# Power.net
KiCad netlist of a schematic drawn in Altium Designer
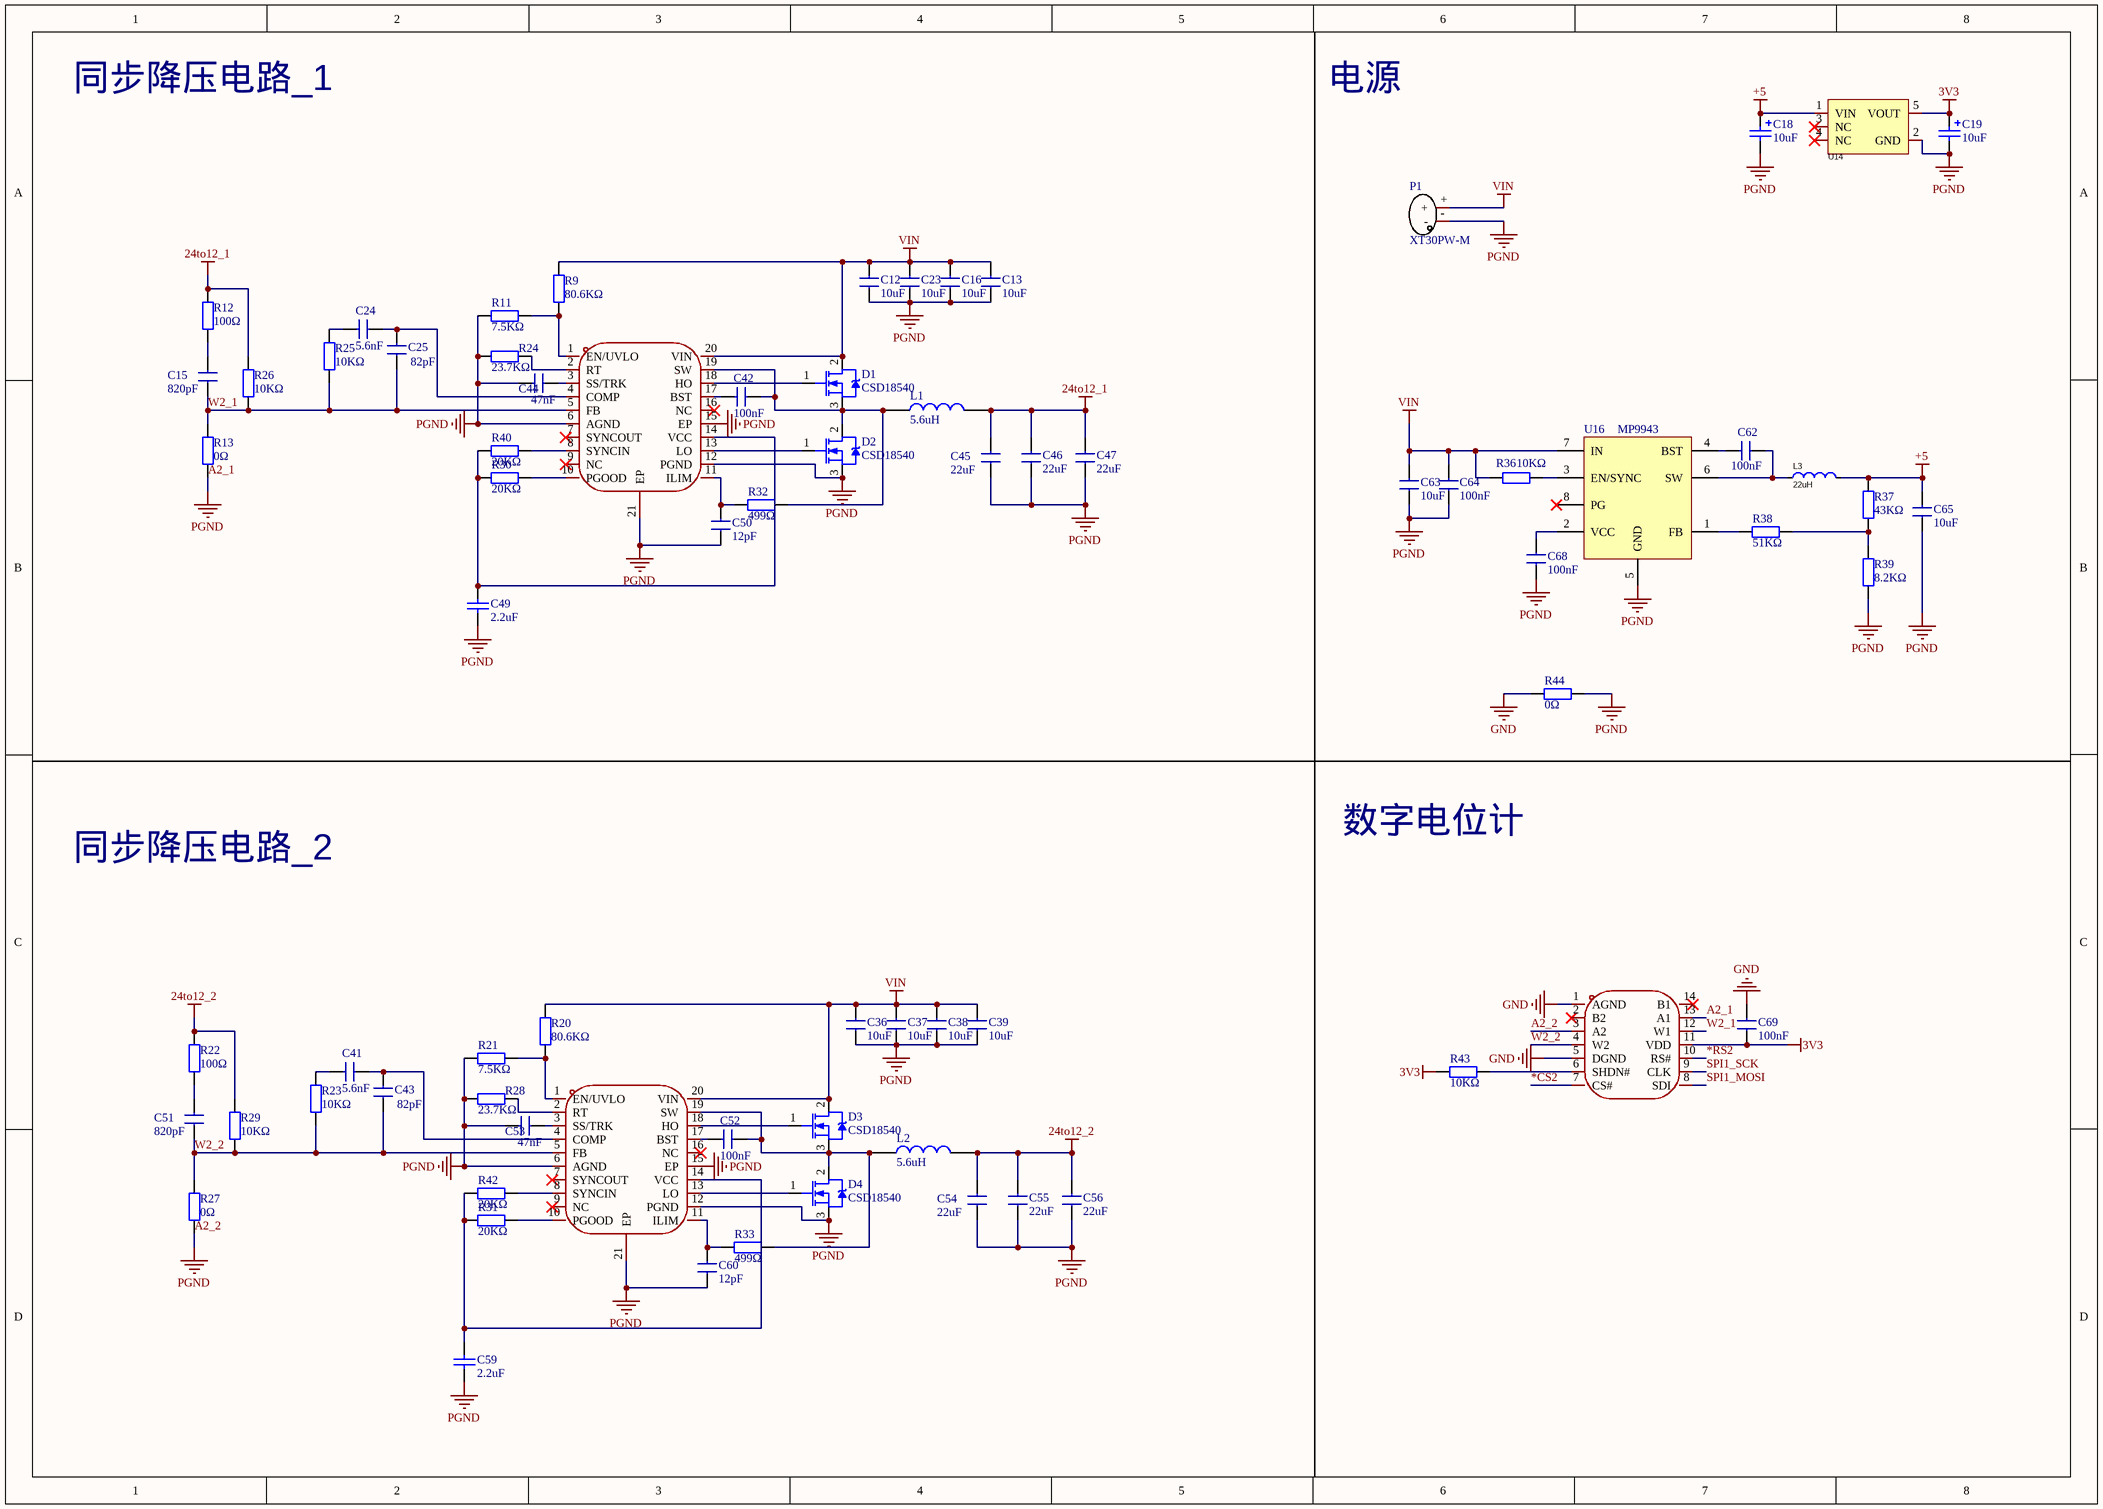
[diagram p0: Power.SchDoc]

(export (version "E")
  (design (tool "Eeschema 10.0.6"))
  (components
    (comp (ref "C12")
      (value "10uF")
      (footprint "1210")
      (description "1210贴片电容")
      (libsource (lib "Integrated_Library1") (part "1210贴片电容"))
    )
    (comp (ref "C13")
      (value "10uF")
      (footprint "1210")
      (description "1210贴片电容")
      (libsource (lib "En") (part "1210贴片电容"))
    )
    (comp (ref "C15")
      (value "820pF")
      (footprint "c0402")
      (description "贴片电容0402")
      (libsource (lib "Integrated_Library1") (part "0402贴片电容"))
    )
    (comp (ref "C16")
      (value "10uF")
      (footprint "1210")
      (description "1210贴片电容")
      (libsource (lib "En") (part "1210贴片电容"))
    )
    (comp (ref "C18")
      (value "10uF")
      (footprint "3216")
      (description "3216钽电容")
      (libsource (lib "Integrated_Library1") (part "3216钽电容"))
    )
    (comp (ref "C19")
      (value "10uF")
      (footprint "3216")
      (description "3216钽电容")
      (libsource (lib "Integrated_Library1") (part "3216钽电容"))
    )
    (comp (ref "C23")
      (value "10uF")
      (footprint "1210")
      (description "1210贴片电容")
      (libsource (lib "En") (part "1210贴片电容"))
    )
    (comp (ref "C24")
      (value "5.6nF")
      (footprint "c0402")
      (description "贴片电容0402")
      (libsource (lib "Integrated_Library1") (part "0402贴片电容"))
    )
    (comp (ref "C25")
      (value "82pF")
      (footprint "c0402")
      (description "贴片电容0402")
      (libsource (lib "Integrated_Library1") (part "0402贴片电容"))
    )
    (comp (ref "C36")
      (value "10uF")
      (footprint "1210")
      (description "1210贴片电容")
      (libsource (lib "Integrated_Library1") (part "1210贴片电容"))
    )
    (comp (ref "C37")
      (value "10uF")
      (footprint "1210")
      (description "1210贴片电容")
      (libsource (lib "En") (part "1210贴片电容"))
    )
    (comp (ref "C38")
      (value "10uF")
      (footprint "1210")
      (description "1210贴片电容")
      (libsource (lib "En") (part "1210贴片电容"))
    )
    (comp (ref "C39")
      (value "10uF")
      (footprint "1210")
      (description "1210贴片电容")
      (libsource (lib "En") (part "1210贴片电容"))
    )
    (comp (ref "C41")
      (value "5.6nF")
      (footprint "c0402")
      (description "贴片电容0402")
      (libsource (lib "Integrated_Library1") (part "0402贴片电容"))
    )
    (comp (ref "C42")
      (value "100nF")
      (footprint "C 0603_M")
      (description "贴片电容0402")
      (libsource (lib "Integrated_Library1") (part "0402贴片电容"))
    )
    (comp (ref "C43")
      (value "82pF")
      (footprint "c0402")
      (description "贴片电容0402")
      (libsource (lib "Integrated_Library1") (part "0402贴片电容"))
    )
    (comp (ref "C44")
      (value "47nF")
      (footprint "c0402")
      (description "贴片电容0402")
      (libsource (lib "Integrated_Library1") (part "0402贴片电容"))
    )
    (comp (ref "C45")
      (value "22uF")
      (footprint "1210")
      (description "1210贴片电容")
      (libsource (lib "En") (part "1210贴片电容"))
    )
    (comp (ref "C46")
      (value "22uF")
      (footprint "1210")
      (description "1210贴片电容")
      (libsource (lib "En") (part "1210贴片电容"))
    )
    (comp (ref "C47")
      (value "22uF")
      (footprint "1210")
      (description "1210贴片电容")
      (libsource (lib "En") (part "1210贴片电容"))
    )
    (comp (ref "C49")
      (value "2.2uF")
      (footprint "C 0603_M")
      (description "0603贴片电容")
      (libsource (lib "En") (part "0603贴片电容"))
    )
    (comp (ref "C50")
      (value "12pF")
      (footprint "c0402")
      (description "贴片电容0402")
      (libsource (lib "Integrated_Library1") (part "0402贴片电容"))
    )
    (comp (ref "C51")
      (value "820pF")
      (footprint "c0402")
      (description "贴片电容0402")
      (libsource (lib "Integrated_Library1") (part "0402贴片电容"))
    )
    (comp (ref "C52")
      (value "100nF")
      (footprint "C 0603_M")
      (description "贴片电容0402")
      (libsource (lib "Integrated_Library1") (part "0402贴片电容"))
    )
    (comp (ref "C53")
      (value "47nF")
      (footprint "c0402")
      (description "贴片电容0402")
      (libsource (lib "Integrated_Library1") (part "0402贴片电容"))
    )
    (comp (ref "C54")
      (value "22uF")
      (footprint "1210")
      (description "1210贴片电容")
      (libsource (lib "En") (part "1210贴片电容"))
    )
    (comp (ref "C55")
      (value "22uF")
      (footprint "1210")
      (description "1210贴片电容")
      (libsource (lib "En") (part "1210贴片电容"))
    )
    (comp (ref "C56")
      (value "22uF")
      (footprint "1210")
      (description "1210贴片电容")
      (libsource (lib "En") (part "1210贴片电容"))
    )
    (comp (ref "C59")
      (value "2.2uF")
      (footprint "C 0603_M")
      (description "0603贴片电容")
      (libsource (lib "En") (part "0603贴片电容"))
    )
    (comp (ref "C60")
      (value "12pF")
      (footprint "c0402")
      (description "贴片电容0402")
      (libsource (lib "Integrated_Library1") (part "0402贴片电容"))
    )
    (comp (ref "C62")
      (value "100nF")
      (footprint "c0402")
      (description "贴片电容0402")
      (libsource (lib "Integrated_Library1") (part "0402贴片电容"))
    )
    (comp (ref "C63")
      (value "10uF")
      (footprint "1210")
      (description "1210贴片电容")
      (libsource (lib "Integrated_Library1") (part "1210贴片电容"))
    )
    (comp (ref "C64")
      (value "100nF")
      (footprint "c0402")
      (description "贴片电容0402")
      (libsource (lib "Integrated_Library1") (part "0402贴片电容"))
    )
    (comp (ref "C65")
      (value "10uF")
      (footprint "1210")
      (description "1210贴片电容")
      (libsource (lib "Integrated_Library1") (part "1210贴片电容"))
    )
    (comp (ref "C68")
      (value "100nF")
      (footprint "c0402")
      (description "贴片电容0402")
      (libsource (lib "Integrated_Library1") (part "0402贴片电容"))
    )
    (comp (ref "C69")
      (value "100nF")
      (footprint "c0402")
      (description "贴片电容0402")
      (libsource (lib "Integrated_Library1") (part "0402贴片电容"))
    )
    (comp (ref "D1")
      (value "CSD18540")
      (footprint "pg-tdson-8")
      (description "N沟道MOS管")
      (fields (field (name "PUBLISHER") "Altium Limited"))
      (libsource (lib "En") (part "CSD18540"))
    )
    (comp (ref "D2")
      (value "CSD18540")
      (footprint "pg-tdson-8")
      (description "N沟道MOS管")
      (fields (field (name "PUBLISHER") "Altium Limited"))
      (libsource (lib "En") (part "CSD18540"))
    )
    (comp (ref "D3")
      (value "CSD18540")
      (footprint "pg-tdson-8")
      (description "N沟道MOS管")
      (fields (field (name "PUBLISHER") "Altium Limited"))
      (libsource (lib "En") (part "CSD18540"))
    )
    (comp (ref "D4")
      (value "CSD18540")
      (footprint "pg-tdson-8")
      (description "N沟道MOS管")
      (fields (field (name "PUBLISHER") "Altium Limited"))
      (libsource (lib "En") (part "CSD18540"))
    )
    (comp (ref "L1")
      (value "5.6uH")
      (footprint "L-SMD-0630")
      (description "一体成型屏蔽电感")
      (libsource (lib "En") (part "0630功率电感"))
    )
    (comp (ref "L2")
      (value "5.6uH")
      (footprint "L-SMD-0630")
      (description "一体成型屏蔽电感")
      (libsource (lib "En") (part "0630功率电感"))
    )
    (comp (ref "L3")
      (value "22uH")
      (footprint "IND-SMD_L5.4-W5.2")
      (description "一体成型屏蔽电感，0530封装，额定电流3A")
      (fields (field (name "MANUFACTURER") "XR(祥如)") (field (name "MANUFACTURER PART") "XR0530-100M"))
      (libsource (lib "En") (part "0530屏蔽电感"))
    )
    (comp (ref "P1")
      (value "XT30PW-M")
      (footprint "XT30PW-M")
      (description "卧式XT30母头")
      (fields (field (name "PUBLISHER") "Altium Limited"))
      (libsource (lib "Integrated_Library1") (part "卧式XT30母头"))
    )
    (comp (ref "R9")
      (value "80.6KΩ")
      (footprint "R0402")
      (description "0402贴片电阻")
      (libsource (lib "") (part "0402贴片电阻_3"))
    )
    (comp (ref "R11")
      (value "7.5KΩ")
      (footprint "R0402")
      (description "0402贴片电阻")
      (libsource (lib "") (part "0402贴片电阻_2"))
    )
    (comp (ref "R12")
      (value "100Ω")
      (footprint "R0402")
      (description "0402贴片电阻")
      (libsource (lib "Integrated_Library1") (part "0402贴片电阻"))
    )
    (comp (ref "R13")
      (value "0Ω")
      (footprint "R0402")
      (description "0402贴片电阻")
      (libsource (lib "") (part "0402贴片电阻_3"))
    )
    (comp (ref "R20")
      (value "80.6KΩ")
      (footprint "R0402")
      (description "0402贴片电阻")
      (libsource (lib "") (part "0402贴片电阻_3"))
    )
    (comp (ref "R21")
      (value "7.5KΩ")
      (footprint "R0402")
      (description "0402贴片电阻")
      (libsource (lib "") (part "0402贴片电阻_2"))
    )
    (comp (ref "R22")
      (value "100Ω")
      (footprint "R0402")
      (description "0402贴片电阻")
      (libsource (lib "Integrated_Library1") (part "0402贴片电阻"))
    )
    (comp (ref "R23")
      (value "10KΩ")
      (footprint "R0402")
      (description "0402贴片电阻")
      (libsource (lib "Integrated_Library1") (part "0402贴片电阻"))
    )
    (comp (ref "R24")
      (value "23.7KΩ")
      (footprint "R0402")
      (description "0402贴片电阻")
      (libsource (lib "") (part "0402贴片电阻_1"))
    )
    (comp (ref "R25")
      (value "10KΩ")
      (footprint "R0402")
      (description "0402贴片电阻")
      (libsource (lib "Integrated_Library1") (part "0402贴片电阻"))
    )
    (comp (ref "R26")
      (value "10KΩ")
      (footprint "R0402")
      (description "0402贴片电阻")
      (libsource (lib "Integrated_Library1") (part "0402贴片电阻"))
    )
    (comp (ref "R27")
      (value "0Ω")
      (footprint "R0402")
      (description "0402贴片电阻")
      (libsource (lib "") (part "0402贴片电阻_3"))
    )
    (comp (ref "R28")
      (value "23.7KΩ")
      (footprint "R0402")
      (description "0402贴片电阻")
      (libsource (lib "") (part "0402贴片电阻_1"))
    )
    (comp (ref "R29")
      (value "10KΩ")
      (footprint "R0402")
      (description "0402贴片电阻")
      (libsource (lib "Integrated_Library1") (part "0402贴片电阻"))
    )
    (comp (ref "R30")
      (value "20KΩ")
      (footprint "R0402")
      (description "0402贴片电阻")
      (libsource (lib "") (part "0402贴片电阻_1"))
    )
    (comp (ref "R31")
      (value "20KΩ")
      (footprint "R0402")
      (description "0402贴片电阻")
      (libsource (lib "") (part "0402贴片电阻_1"))
    )
    (comp (ref "R32")
      (value "499Ω")
      (footprint "R0402")
      (description "0402贴片电阻")
      (libsource (lib "") (part "0402贴片电阻_1"))
    )
    (comp (ref "R33")
      (value "499Ω")
      (footprint "R0402")
      (description "0402贴片电阻")
      (libsource (lib "") (part "0402贴片电阻_1"))
    )
    (comp (ref "R36")
      (value "10KΩ")
      (footprint "R0402")
      (description "0402贴片电阻")
      (libsource (lib "") (part "0402贴片电阻_2"))
    )
    (comp (ref "R37")
      (value "43KΩ")
      (footprint "R0402")
      (description "0402贴片电阻")
      (libsource (lib "Integrated_Library1") (part "0402贴片电阻"))
    )
    (comp (ref "R38")
      (value "51KΩ")
      (footprint "R0402")
      (description "0402贴片电阻")
      (libsource (lib "") (part "0402贴片电阻_2"))
    )
    (comp (ref "R39")
      (value "8.2KΩ")
      (footprint "R0402")
      (description "0402贴片电阻")
      (libsource (lib "Integrated_Library1") (part "0402贴片电阻"))
    )
    (comp (ref "R40")
      (value "20KΩ")
      (footprint "R0402")
      (description "0402贴片电阻")
      (libsource (lib "") (part "0402贴片电阻_1"))
    )
    (comp (ref "R42")
      (value "20KΩ")
      (footprint "R0402")
      (description "0402贴片电阻")
      (libsource (lib "") (part "0402贴片电阻_1"))
    )
    (comp (ref "R43")
      (value "10KΩ")
      (footprint "R0402")
      (description "0402贴片电阻")
      (libsource (lib "") (part "0402贴片电阻_1"))
    )
    (comp (ref "R44")
      (value "0Ω")
      (footprint "R0402")
      (description "0402贴片电阻")
      (libsource (lib "") (part "0402贴片电阻_2"))
    )
    (comp (ref "U7")
      (value "LM25145RGYR")
      (footprint "VQFN-20_L4.5-W3.5-P0.50-BL-EP")
      (fields (field (name "MANUFACTURER") "TI(德州仪器)"))
      (libsource (lib "Schlib1") (part "LM25145RGYR"))
    )
    (comp (ref "U13")
      (value "LM25145RGYR")
      (footprint "VQFN-20_L4.5-W3.5-P0.50-BL-EP")
      (fields (field (name "MANUFACTURER") "TI(德州仪器)"))
      (libsource (lib "Schlib1") (part "LM25145RGYR"))
    )
    (comp (ref "U14")
      (value "XC6201P332MR-HXY")
      (footprint "SOT-23-5_L3.0-W1.7-P0.95-LS2.8-BR")
      (description "3.3V LDO")
      (fields (field (name "MANUFACTURER") "HXY MOSFET(华轩阳电子)"))
      (libsource (lib "Integrated_Library1") (part "XC6201P332MR-HXY"))
    )
    (comp (ref "U16")
      (value "MP9943")
      (footprint "QFN-8 3x3")
      (libsource (lib "Integrated_Library1") (part "MP9943"))
    )
    (comp (ref "U17")
      (value "AD8402ARZ10-REEL")
      (footprint "SOIC-14_L8.7-W3.9-P1.27-LS6.0-BL")
      (fields (field (name "MANUFACTURER") "ADI(亚德诺)"))
      (libsource (lib "Schlib1") (part "AD8402ARZ10-REEL"))
    )
  )
  (nets
    (net (code "1") (name "+5") (class "Default")
      (node (ref "C18") (pin "1") (pinfunction "1_1") (pintype "passive"))
      (node (ref "C65") (pin "2") (pinfunction "2_2") (pintype "passive"))
      (node (ref "L3") (pin "2") (pinfunction "2_2") (pintype "passive"))
      (node (ref "R37") (pin "2") (pinfunction "2_2") (pintype "passive"))
      (node (ref "U14") (pin "1") (pinfunction "VIN_1") (pintype "passive"))
    )
    (net (code "2") (name "/*CS2") (class "Default")
      (node (ref "U17") (pin "7") (pinfunction "CS#_7") (pintype "passive"))
    )
    (net (code "3") (name "/*RS2") (class "Default")
      (node (ref "U17") (pin "10") (pinfunction "RS#_10") (pintype "passive"))
    )
    (net (code "4") (name "/SPI1_MOSI") (class "Default")
      (node (ref "U17") (pin "8") (pinfunction "SDI_8") (pintype "passive"))
    )
    (net (code "5") (name "/SPI1_SCK") (class "Default")
      (node (ref "U17") (pin "9") (pinfunction "CLK_9") (pintype "passive"))
    )
    (net (code "6") (name "/W2_1") (class "Default")
      (node (ref "C15") (pin "2") (pinfunction "2_2") (pintype "passive"))
      (node (ref "C25") (pin "1") (pinfunction "1_1") (pintype "passive"))
      (node (ref "R13") (pin "1") (pinfunction "1_1") (pintype "passive"))
      (node (ref "R25") (pin "1") (pinfunction "1_1") (pintype "passive"))
      (node (ref "R26") (pin "1") (pinfunction "1_1") (pintype "passive"))
      (node (ref "U13") (pin "5") (pinfunction "FB_5") (pintype "passive"))
      (node (ref "U17") (pin "12") (pinfunction "W1_12") (pintype "passive"))
    )
    (net (code "7") (name "/W2_2") (class "Default")
      (node (ref "C43") (pin "1") (pinfunction "1_1") (pintype "passive"))
      (node (ref "C51") (pin "2") (pinfunction "2_2") (pintype "passive"))
      (node (ref "R23") (pin "1") (pinfunction "1_1") (pintype "passive"))
      (node (ref "R27") (pin "1") (pinfunction "1_1") (pintype "passive"))
      (node (ref "R29") (pin "1") (pinfunction "1_1") (pintype "passive"))
      (node (ref "U17") (pin "4") (pinfunction "W2_4") (pintype "passive"))
      (node (ref "U7") (pin "5") (pinfunction "FB_5") (pintype "passive"))
    )
    (net (code "8") (name "3V3") (class "Default")
      (node (ref "C19") (pin "1") (pinfunction "1_1") (pintype "passive"))
      (node (ref "C69") (pin "2") (pinfunction "2_2") (pintype "passive"))
      (node (ref "R43") (pin "2") (pinfunction "2_2") (pintype "passive"))
      (node (ref "U14") (pin "5") (pinfunction "VOUT_5") (pintype "passive"))
      (node (ref "U17") (pin "11") (pinfunction "VDD_11") (pintype "passive"))
    )
    (net (code "9") (name "24to12_1") (class "Default")
      (node (ref "C45") (pin "2") (pinfunction "2_2") (pintype "passive"))
      (node (ref "C46") (pin "2") (pinfunction "2_2") (pintype "passive"))
      (node (ref "C47") (pin "2") (pinfunction "2_2") (pintype "passive"))
      (node (ref "L1") (pin "2") (pinfunction "2_2") (pintype "passive"))
      (node (ref "R12") (pin "2") (pinfunction "2_2") (pintype "passive"))
      (node (ref "R26") (pin "2") (pinfunction "2_2") (pintype "passive"))
    )
    (net (code "10") (name "24to12_2") (class "Default")
      (node (ref "C54") (pin "2") (pinfunction "2_2") (pintype "passive"))
      (node (ref "C55") (pin "2") (pinfunction "2_2") (pintype "passive"))
      (node (ref "C56") (pin "2") (pinfunction "2_2") (pintype "passive"))
      (node (ref "L2") (pin "2") (pinfunction "2_2") (pintype "passive"))
      (node (ref "R22") (pin "2") (pinfunction "2_2") (pintype "passive"))
      (node (ref "R29") (pin "2") (pinfunction "2_2") (pintype "passive"))
    )
    (net (code "11") (name "GND") (class "Default")
      (node (ref "C69") (pin "1") (pinfunction "1_1") (pintype "passive"))
      (node (ref "R44") (pin "1") (pinfunction "1_1") (pintype "passive"))
      (node (ref "U17") (pin "1") (pinfunction "AGND_1") (pintype "passive"))
      (node (ref "U17") (pin "5") (pinfunction "DGND_5") (pintype "passive"))
    )
    (net (code "12") (name "Net-(C15-Pad1)") (class "Default")
      (node (ref "C15") (pin "1") (pinfunction "1_1") (pintype "passive"))
      (node (ref "R12") (pin "1") (pinfunction "1_1") (pintype "passive"))
    )
    (net (code "13") (name "Net-(C24-Pad2)") (class "Default")
      (node (ref "C24") (pin "2") (pinfunction "2_2") (pintype "passive"))
      (node (ref "R25") (pin "2") (pinfunction "2_2") (pintype "passive"))
    )
    (net (code "14") (name "Net-(C41-Pad2)") (class "Default")
      (node (ref "C41") (pin "2") (pinfunction "2_2") (pintype "passive"))
      (node (ref "R23") (pin "2") (pinfunction "2_2") (pintype "passive"))
    )
    (net (code "15") (name "Net-(C51-Pad1)") (class "Default")
      (node (ref "C51") (pin "1") (pinfunction "1_1") (pintype "passive"))
      (node (ref "R22") (pin "1") (pinfunction "1_1") (pintype "passive"))
    )
    (net (code "16") (name "Net-(D1-G)") (class "Default")
      (node (ref "D1") (pin "1") (pinfunction "G_1") (pintype "passive"))
      (node (ref "U13") (pin "18") (pinfunction "HO_18") (pintype "passive"))
    )
    (net (code "17") (name "Net-(D1-S)") (class "Default")
      (node (ref "C42") (pin "1") (pinfunction "1_1") (pintype "passive"))
      (node (ref "D1") (pin "3") (pinfunction "S_3") (pintype "passive"))
      (node (ref "D2") (pin "2") (pinfunction "D_2") (pintype "passive"))
      (node (ref "L1") (pin "1") (pinfunction "1_1") (pintype "passive"))
      (node (ref "R32") (pin "1") (pinfunction "1_1") (pintype "passive"))
      (node (ref "U13") (pin "19") (pinfunction "SW_19") (pintype "passive"))
    )
    (net (code "18") (name "Net-(D2-G)") (class "Default")
      (node (ref "D2") (pin "1") (pinfunction "G_1") (pintype "passive"))
      (node (ref "U13") (pin "13") (pinfunction "LO_13") (pintype "passive"))
    )
    (net (code "19") (name "Net-(D3-G)") (class "Default")
      (node (ref "D3") (pin "1") (pinfunction "G_1") (pintype "passive"))
      (node (ref "U7") (pin "18") (pinfunction "HO_18") (pintype "passive"))
    )
    (net (code "20") (name "Net-(D3-S)") (class "Default")
      (node (ref "C52") (pin "1") (pinfunction "1_1") (pintype "passive"))
      (node (ref "D3") (pin "3") (pinfunction "S_3") (pintype "passive"))
      (node (ref "D4") (pin "2") (pinfunction "D_2") (pintype "passive"))
      (node (ref "L2") (pin "1") (pinfunction "1_1") (pintype "passive"))
      (node (ref "R33") (pin "1") (pinfunction "1_1") (pintype "passive"))
      (node (ref "U7") (pin "19") (pinfunction "SW_19") (pintype "passive"))
    )
    (net (code "21") (name "Net-(D4-G)") (class "Default")
      (node (ref "D4") (pin "1") (pinfunction "G_1") (pintype "passive"))
      (node (ref "U7") (pin "13") (pinfunction "LO_13") (pintype "passive"))
    )
    (net (code "22") (name "Net-(R37-Pad1)") (class "Default")
      (node (ref "R37") (pin "1") (pinfunction "1_1") (pintype "passive"))
      (node (ref "R38") (pin "2") (pinfunction "2_2") (pintype "passive"))
      (node (ref "R39") (pin "2") (pinfunction "2_2") (pintype "passive"))
    )
    (net (code "23") (name "Net-(U7-BST)") (class "Default")
      (node (ref "C52") (pin "2") (pinfunction "2_2") (pintype "passive"))
      (node (ref "U7") (pin "17") (pinfunction "BST_17") (pintype "passive"))
    )
    (net (code "24") (name "Net-(U7-COMP)") (class "Default")
      (node (ref "C41") (pin "1") (pinfunction "1_1") (pintype "passive"))
      (node (ref "C43") (pin "2") (pinfunction "2_2") (pintype "passive"))
      (node (ref "U7") (pin "4") (pinfunction "COMP_4") (pintype "passive"))
    )
    (net (code "25") (name "Net-(U7-EN{slash}UVLO)") (class "Default")
      (node (ref "R20") (pin "2") (pinfunction "2_2") (pintype "passive"))
      (node (ref "R21") (pin "2") (pinfunction "2_2") (pintype "passive"))
      (node (ref "U7") (pin "1") (pinfunction "EN/UVLO_1") (pintype "passive"))
    )
    (net (code "26") (name "Net-(U7-ILIM)") (class "Default")
      (node (ref "C60") (pin "2") (pinfunction "2_2") (pintype "passive"))
      (node (ref "R33") (pin "2") (pinfunction "2_2") (pintype "passive"))
      (node (ref "U7") (pin "11") (pinfunction "ILIM_11") (pintype "passive"))
    )
    (net (code "27") (name "Net-(U7-PGOOD)") (class "Default")
      (node (ref "R31") (pin "1") (pinfunction "1_1") (pintype "passive"))
      (node (ref "U7") (pin "10") (pinfunction "PGOOD_10") (pintype "passive"))
    )
    (net (code "28") (name "Net-(U7-RT)") (class "Default")
      (node (ref "R28") (pin "1") (pinfunction "1_1") (pintype "passive"))
      (node (ref "U7") (pin "2") (pinfunction "RT_2") (pintype "passive"))
    )
    (net (code "29") (name "Net-(U7-SS{slash}TRK)") (class "Default")
      (node (ref "C53") (pin "1") (pinfunction "1_1") (pintype "passive"))
      (node (ref "U7") (pin "3") (pinfunction "SS/TRK_3") (pintype "passive"))
    )
    (net (code "30") (name "Net-(U7-SYNCIN)") (class "Default")
      (node (ref "R42") (pin "1") (pinfunction "1_1") (pintype "passive"))
      (node (ref "U7") (pin "8") (pinfunction "SYNCIN_8") (pintype "passive"))
    )
    (net (code "31") (name "Net-(U7-VCC)") (class "Default")
      (node (ref "C59") (pin "2") (pinfunction "2_2") (pintype "passive"))
      (node (ref "R31") (pin "2") (pinfunction "2_2") (pintype "passive"))
      (node (ref "R42") (pin "2") (pinfunction "2_2") (pintype "passive"))
      (node (ref "U7") (pin "14") (pinfunction "VCC_14") (pintype "passive"))
    )
    (net (code "32") (name "Net-(U13-BST)") (class "Default")
      (node (ref "C42") (pin "2") (pinfunction "2_2") (pintype "passive"))
      (node (ref "U13") (pin "17") (pinfunction "BST_17") (pintype "passive"))
    )
    (net (code "33") (name "Net-(U13-COMP)") (class "Default")
      (node (ref "C24") (pin "1") (pinfunction "1_1") (pintype "passive"))
      (node (ref "C25") (pin "2") (pinfunction "2_2") (pintype "passive"))
      (node (ref "U13") (pin "4") (pinfunction "COMP_4") (pintype "passive"))
    )
    (net (code "34") (name "Net-(U13-EN{slash}UVLO)") (class "Default")
      (node (ref "R11") (pin "2") (pinfunction "2_2") (pintype "passive"))
      (node (ref "R9") (pin "2") (pinfunction "2_2") (pintype "passive"))
      (node (ref "U13") (pin "1") (pinfunction "EN/UVLO_1") (pintype "passive"))
    )
    (net (code "35") (name "Net-(U13-ILIM)") (class "Default")
      (node (ref "C50") (pin "2") (pinfunction "2_2") (pintype "passive"))
      (node (ref "R32") (pin "2") (pinfunction "2_2") (pintype "passive"))
      (node (ref "U13") (pin "11") (pinfunction "ILIM_11") (pintype "passive"))
    )
    (net (code "36") (name "Net-(U13-PGOOD)") (class "Default")
      (node (ref "R30") (pin "1") (pinfunction "1_1") (pintype "passive"))
      (node (ref "U13") (pin "10") (pinfunction "PGOOD_10") (pintype "passive"))
    )
    (net (code "37") (name "Net-(U13-RT)") (class "Default")
      (node (ref "R24") (pin "1") (pinfunction "1_1") (pintype "passive"))
      (node (ref "U13") (pin "2") (pinfunction "RT_2") (pintype "passive"))
    )
    (net (code "38") (name "Net-(U13-SS{slash}TRK)") (class "Default")
      (node (ref "C44") (pin "1") (pinfunction "1_1") (pintype "passive"))
      (node (ref "U13") (pin "3") (pinfunction "SS/TRK_3") (pintype "passive"))
    )
    (net (code "39") (name "Net-(U13-SYNCIN)") (class "Default")
      (node (ref "R40") (pin "1") (pinfunction "1_1") (pintype "passive"))
      (node (ref "U13") (pin "8") (pinfunction "SYNCIN_8") (pintype "passive"))
    )
    (net (code "40") (name "Net-(U13-VCC)") (class "Default")
      (node (ref "C49") (pin "2") (pinfunction "2_2") (pintype "passive"))
      (node (ref "R30") (pin "2") (pinfunction "2_2") (pintype "passive"))
      (node (ref "R40") (pin "2") (pinfunction "2_2") (pintype "passive"))
      (node (ref "U13") (pin "14") (pinfunction "VCC_14") (pintype "passive"))
    )
    (net (code "41") (name "Net-(U16-BST)") (class "Default")
      (node (ref "C62") (pin "1") (pinfunction "1_1") (pintype "passive"))
      (node (ref "U16") (pin "4") (pinfunction "BST_4") (pintype "passive"))
    )
    (net (code "42") (name "Net-(U16-EN{slash}SYNC)") (class "Default")
      (node (ref "R36") (pin "2") (pinfunction "2_2") (pintype "passive"))
      (node (ref "U16") (pin "3") (pinfunction "EN/SYNC_3") (pintype "passive"))
    )
    (net (code "43") (name "Net-(U16-FB)") (class "Default")
      (node (ref "R38") (pin "1") (pinfunction "1_1") (pintype "passive"))
      (node (ref "U16") (pin "1") (pinfunction "FB_1") (pintype "passive"))
    )
    (net (code "44") (name "Net-(U16-SW)") (class "Default")
      (node (ref "C62") (pin "2") (pinfunction "2_2") (pintype "passive"))
      (node (ref "L3") (pin "1") (pinfunction "1_1") (pintype "passive"))
      (node (ref "U16") (pin "6") (pinfunction "SW_6") (pintype "passive"))
    )
    (net (code "45") (name "Net-(U16-VCC)") (class "Default")
      (node (ref "C68") (pin "2") (pinfunction "2_2") (pintype "passive"))
      (node (ref "U16") (pin "2") (pinfunction "VCC_2") (pintype "passive"))
    )
    (net (code "46") (name "Net-(U17-SHDN#)") (class "Default")
      (node (ref "R43") (pin "1") (pinfunction "1_1") (pintype "passive"))
      (node (ref "U17") (pin "6") (pinfunction "SHDN#_6") (pintype "passive"))
    )
    (net (code "47") (name "PGND") (class "Default")
      (node (ref "C12") (pin "1") (pinfunction "1_1") (pintype "passive"))
      (node (ref "C13") (pin "1") (pinfunction "1_1") (pintype "passive"))
      (node (ref "C16") (pin "1") (pinfunction "1_1") (pintype "passive"))
      (node (ref "C18") (pin "2") (pinfunction "2_2") (pintype "passive"))
      (node (ref "C19") (pin "2") (pinfunction "2_2") (pintype "passive"))
      (node (ref "C23") (pin "1") (pinfunction "1_1") (pintype "passive"))
      (node (ref "C36") (pin "1") (pinfunction "1_1") (pintype "passive"))
      (node (ref "C37") (pin "1") (pinfunction "1_1") (pintype "passive"))
      (node (ref "C38") (pin "1") (pinfunction "1_1") (pintype "passive"))
      (node (ref "C39") (pin "1") (pinfunction "1_1") (pintype "passive"))
      (node (ref "C44") (pin "2") (pinfunction "2_2") (pintype "passive"))
      (node (ref "C45") (pin "1") (pinfunction "1_1") (pintype "passive"))
      (node (ref "C46") (pin "1") (pinfunction "1_1") (pintype "passive"))
      (node (ref "C47") (pin "1") (pinfunction "1_1") (pintype "passive"))
      (node (ref "C49") (pin "1") (pinfunction "1_1") (pintype "passive"))
      (node (ref "C50") (pin "1") (pinfunction "1_1") (pintype "passive"))
      (node (ref "C53") (pin "2") (pinfunction "2_2") (pintype "passive"))
      (node (ref "C54") (pin "1") (pinfunction "1_1") (pintype "passive"))
      (node (ref "C55") (pin "1") (pinfunction "1_1") (pintype "passive"))
      (node (ref "C56") (pin "1") (pinfunction "1_1") (pintype "passive"))
      (node (ref "C59") (pin "1") (pinfunction "1_1") (pintype "passive"))
      (node (ref "C60") (pin "1") (pinfunction "1_1") (pintype "passive"))
      (node (ref "C63") (pin "1") (pinfunction "1_1") (pintype "passive"))
      (node (ref "C64") (pin "1") (pinfunction "1_1") (pintype "passive"))
      (node (ref "C65") (pin "1") (pinfunction "1_1") (pintype "passive"))
      (node (ref "C68") (pin "1") (pinfunction "1_1") (pintype "passive"))
      (node (ref "D2") (pin "3") (pinfunction "S_3") (pintype "passive"))
      (node (ref "D4") (pin "3") (pinfunction "S_3") (pintype "passive"))
      (node (ref "P1") (pin "-") (pinfunction "-_-") (pintype "passive"))
      (node (ref "R11") (pin "1") (pinfunction "1_1") (pintype "passive"))
      (node (ref "R13") (pin "2") (pinfunction "2_2") (pintype "passive"))
      (node (ref "R21") (pin "1") (pinfunction "1_1") (pintype "passive"))
      (node (ref "R24") (pin "2") (pinfunction "2_2") (pintype "passive"))
      (node (ref "R27") (pin "2") (pinfunction "2_2") (pintype "passive"))
      (node (ref "R28") (pin "2") (pinfunction "2_2") (pintype "passive"))
      (node (ref "R39") (pin "1") (pinfunction "1_1") (pintype "passive"))
      (node (ref "R44") (pin "2") (pinfunction "2_2") (pintype "passive"))
      (node (ref "U13") (pin "12") (pinfunction "PGND_12") (pintype "passive"))
      (node (ref "U13") (pin "15") (pinfunction "EP_15") (pintype "passive"))
      (node (ref "U13") (pin "21") (pinfunction "EP_21") (pintype "passive"))
      (node (ref "U13") (pin "6") (pinfunction "AGND_6") (pintype "passive"))
      (node (ref "U14") (pin "2") (pinfunction "GND_2") (pintype "passive"))
      (node (ref "U16") (pin "5") (pinfunction "GND_5") (pintype "passive"))
      (node (ref "U17") (pin "13") (pinfunction "A1_13") (pintype "passive"))
      (node (ref "U17") (pin "3") (pinfunction "A2_3") (pintype "passive"))
      (node (ref "U7") (pin "12") (pinfunction "PGND_12") (pintype "passive"))
      (node (ref "U7") (pin "15") (pinfunction "EP_15") (pintype "passive"))
      (node (ref "U7") (pin "21") (pinfunction "EP_21") (pintype "passive"))
      (node (ref "U7") (pin "6") (pinfunction "AGND_6") (pintype "passive"))
    )
    (net (code "48") (name "VIN") (class "Default")
      (node (ref "C12") (pin "2") (pinfunction "2_2") (pintype "passive"))
      (node (ref "C13") (pin "2") (pinfunction "2_2") (pintype "passive"))
      (node (ref "C16") (pin "2") (pinfunction "2_2") (pintype "passive"))
      (node (ref "C23") (pin "2") (pinfunction "2_2") (pintype "passive"))
      (node (ref "C36") (pin "2") (pinfunction "2_2") (pintype "passive"))
      (node (ref "C37") (pin "2") (pinfunction "2_2") (pintype "passive"))
      (node (ref "C38") (pin "2") (pinfunction "2_2") (pintype "passive"))
      (node (ref "C39") (pin "2") (pinfunction "2_2") (pintype "passive"))
      (node (ref "C63") (pin "2") (pinfunction "2_2") (pintype "passive"))
      (node (ref "C64") (pin "2") (pinfunction "2_2") (pintype "passive"))
      (node (ref "D1") (pin "2") (pinfunction "D_2") (pintype "passive"))
      (node (ref "D3") (pin "2") (pinfunction "D_2") (pintype "passive"))
      (node (ref "P1") (pin "+") (pinfunction "+_+") (pintype "passive"))
      (node (ref "R20") (pin "1") (pinfunction "1_1") (pintype "passive"))
      (node (ref "R36") (pin "1") (pinfunction "1_1") (pintype "passive"))
      (node (ref "R9") (pin "1") (pinfunction "1_1") (pintype "passive"))
      (node (ref "U13") (pin "20") (pinfunction "VIN_20") (pintype "passive"))
      (node (ref "U16") (pin "7") (pinfunction "IN_7") (pintype "passive"))
      (node (ref "U7") (pin "20") (pinfunction "VIN_20") (pintype "passive"))
    )
    (net (code "49") (name "unconnected-(U7-NC-Pad9)") (class "Default")
      (node (ref "U7") (pin "9") (pinfunction "NC_9") (pintype "passive+no_connect"))
    )
    (net (code "50") (name "unconnected-(U7-NC-Pad16)") (class "Default")
      (node (ref "U7") (pin "16") (pinfunction "NC_16") (pintype "passive+no_connect"))
    )
    (net (code "51") (name "unconnected-(U7-SYNCOUT-Pad7)") (class "Default")
      (node (ref "U7") (pin "7") (pinfunction "SYNCOUT_7") (pintype "passive+no_connect"))
    )
    (net (code "52") (name "unconnected-(U13-NC-Pad9)") (class "Default")
      (node (ref "U13") (pin "9") (pinfunction "NC_9") (pintype "passive+no_connect"))
    )
    (net (code "53") (name "unconnected-(U13-NC-Pad16)") (class "Default")
      (node (ref "U13") (pin "16") (pinfunction "NC_16") (pintype "passive+no_connect"))
    )
    (net (code "54") (name "unconnected-(U13-SYNCOUT-Pad7)") (class "Default")
      (node (ref "U13") (pin "7") (pinfunction "SYNCOUT_7") (pintype "passive+no_connect"))
    )
    (net (code "55") (name "unconnected-(U14-NC-Pad3)") (class "Default")
      (node (ref "U14") (pin "3") (pinfunction "NC_3") (pintype "passive+no_connect"))
    )
    (net (code "56") (name "unconnected-(U14-NC-Pad4)") (class "Default")
      (node (ref "U14") (pin "4") (pinfunction "NC_4") (pintype "passive+no_connect"))
    )
    (net (code "57") (name "unconnected-(U16-PG-Pad8)") (class "Default")
      (node (ref "U16") (pin "8") (pinfunction "PG_8") (pintype "passive+no_connect"))
    )
    (net (code "58") (name "unconnected-(U17-B1-Pad14)") (class "Default")
      (node (ref "U17") (pin "14") (pinfunction "B1_14") (pintype "passive+no_connect"))
    )
    (net (code "59") (name "unconnected-(U17-B2-Pad2)") (class "Default")
      (node (ref "U17") (pin "2") (pinfunction "B2_2") (pintype "passive+no_connect"))
    )
  )
)
